# LoRa_E32_STM32F4.net
KiCad netlist of a schematic drawn in EAGLE
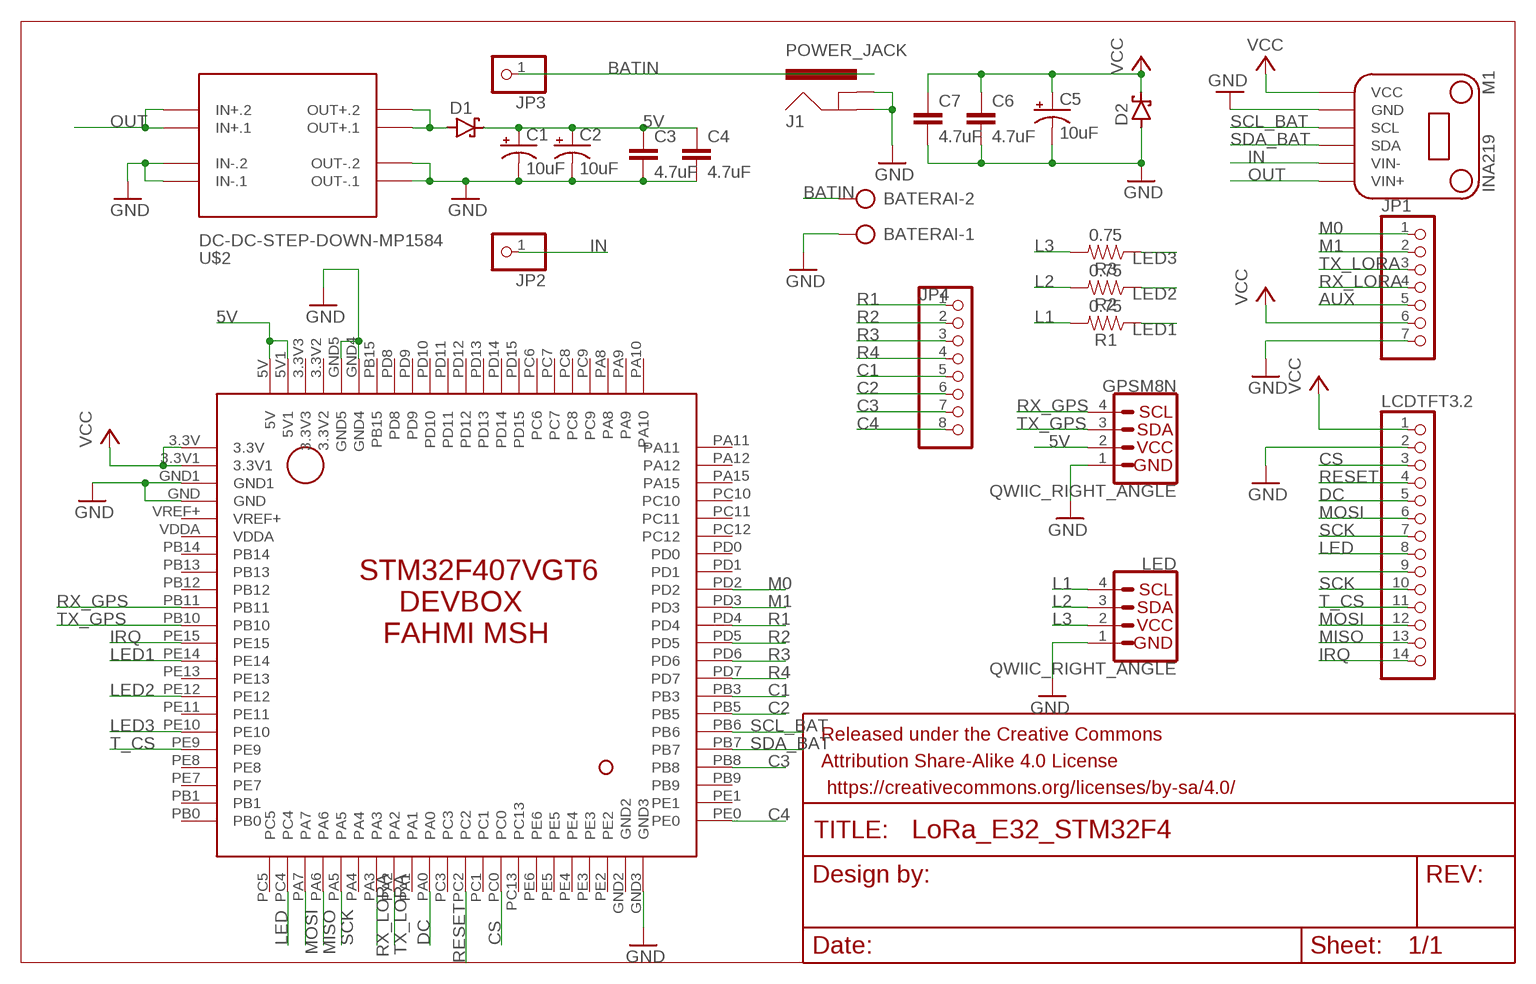
[diagram p0: schematic, sheet 1]

(export (version "E")
  (design (tool "Eeschema 10.0.6"))
  (components
    (comp (ref "BATERAI")
      (value "AK500/2")
      (footprint "eagle-import:AK500_2")
      (libsource (lib "eagle-import") (part "AK500/2"))
    )
    (comp (ref "C1")
      (value "10uF")
      (footprint "eagle-import:EIA3216")
      (libsource (lib "eagle-import") (part "10UF-POLAR-EIA3216-16V-10%(TANT)"))
    )
    (comp (ref "C2")
      (value "10uF")
      (footprint "eagle-import:EIA3216")
      (libsource (lib "eagle-import") (part "10UF-POLAR-EIA3216-16V-10%(TANT)"))
    )
    (comp (ref "C3")
      (value "4.7uF")
      (footprint "eagle-import:0805")
      (libsource (lib "eagle-import") (part "4.7UF-0805-50V-(10%)"))
    )
    (comp (ref "C4")
      (value "4.7uF")
      (footprint "eagle-import:0805")
      (libsource (lib "eagle-import") (part "4.7UF-0805-50V-(10%)"))
    )
    (comp (ref "C5")
      (value "10uF")
      (footprint "eagle-import:EIA3216")
      (libsource (lib "eagle-import") (part "10UF-POLAR-EIA3216-16V-10%(TANT)"))
    )
    (comp (ref "C6")
      (value "4.7uF")
      (footprint "eagle-import:0805")
      (libsource (lib "eagle-import") (part "4.7UF-0805-50V-(10%)"))
    )
    (comp (ref "C7")
      (value "4.7uF")
      (footprint "eagle-import:0805")
      (libsource (lib "eagle-import") (part "4.7UF-0805-50V-(10%)"))
    )
    (comp (ref "D1")
      (value "SCHOTTKY-DIODESMD")
      (footprint "eagle-import:SMB")
      (libsource (lib "eagle-import") (part "SCHOTTKY-DIODESMD"))
    )
    (comp (ref "D2")
      (value "SCHOTTKY-DIODESMD")
      (footprint "eagle-import:SMB")
      (libsource (lib "eagle-import") (part "SCHOTTKY-DIODESMD"))
    )
    (comp (ref "FRAME1")
      (value "FRAME-LEDGER")
      (footprint "eagle-import:CREATIVE_COMMONS")
      (libsource (lib "eagle-import") (part "FRAME-LEDGER"))
    )
    (comp (ref "GPSM8N")
      (value "QWIIC_RIGHT_ANGLE")
      (footprint "eagle-import:JST04_1MM_RA")
      (libsource (lib "eagle-import") (part "QWIIC_CONNECTORJS-1MM"))
    )
    (comp (ref "J1")
      (value "POWER_JACK")
      (footprint "eagle-import:POWER_JACK_PTH")
      (libsource (lib "eagle-import") (part "POWER_JACK"))
    )
    (comp (ref "JP1")
      (value "PINHD-1X7")
      (footprint "eagle-import:1X07")
      (libsource (lib "eagle-import") (part "PINHD-1X7"))
    )
    (comp (ref "JP2")
      (value "PINHD-1X1")
      (footprint "eagle-import:1X01")
      (libsource (lib "eagle-import") (part "PINHD-1X1"))
    )
    (comp (ref "JP3")
      (value "PINHD-1X1")
      (footprint "eagle-import:1X01")
      (libsource (lib "eagle-import") (part "PINHD-1X1"))
    )
    (comp (ref "JP4")
      (value "PINHD-1X8/90")
      (footprint "eagle-import:1X08_90")
      (libsource (lib "eagle-import") (part "PINHD-1X8/90"))
    )
    (comp (ref "LCDTFT3.2")
      (value "PINHD-1X14")
      (footprint "eagle-import:1X14")
      (libsource (lib "eagle-import") (part "PINHD-1X14"))
    )
    (comp (ref "LED")
      (value "QWIIC_RIGHT_ANGLE")
      (footprint "eagle-import:JST04_1MM_RA")
      (libsource (lib "eagle-import") (part "QWIIC_CONNECTORJS-1MM"))
    )
    (comp (ref "M1")
      (value "INA219")
      (footprint "eagle-import:INA219")
      (libsource (lib "eagle-import") (part "INA219"))
    )
    (comp (ref "R1")
      (value "0.75")
      (footprint "eagle-import:0805")
      (libsource (lib "eagle-import") (part "0.75OHM-0805-1/4W-1%"))
    )
    (comp (ref "R2")
      (value "0.75")
      (footprint "eagle-import:0805")
      (libsource (lib "eagle-import") (part "0.75OHM-0805-1/4W-1%"))
    )
    (comp (ref "R3")
      (value "0.75")
      (footprint "eagle-import:0805")
      (libsource (lib "eagle-import") (part "0.75OHM-0805-1/4W-1%"))
    )
    (comp (ref "U$1")
      (value "STM32F4DEVBOX")
      (footprint "eagle-import:STM32F4DEVBOX")
      (libsource (lib "eagle-import") (part "STM32F4DEVBOX"))
    )
    (comp (ref "U$2")
      (value "DC-DC-STEP-DOWN-MP1584")
      (footprint "eagle-import:DC-DC-STEP-DOWN-MP1584")
      (libsource (lib "eagle-import") (part "DC-DC-STEP-DOWN-MP1584"))
    )
  )
  (nets
    (net (code "1") (name "/5V") (class "Default")
      (node (ref "C1") (pin "+") (pinfunction "+_+") (pintype "passive"))
      (node (ref "C2") (pin "+") (pinfunction "+_+") (pintype "passive"))
      (node (ref "C3") (pin "1") (pinfunction "1_1") (pintype "passive"))
      (node (ref "C4") (pin "1") (pinfunction "1_1") (pintype "passive"))
      (node (ref "D1") (pin "C") (pinfunction "C_C") (pintype "passive"))
      (node (ref "GPSM8N") (pin "2") (pinfunction "2_2") (pintype "power_in"))
      (node (ref "U$1") (pin "5V") (pinfunction "5V_5V") (pintype "bidirectional"))
      (node (ref "U$1") (pin "5V1") (pinfunction "5V1_5V1") (pintype "bidirectional"))
    )
    (net (code "2") (name "/AUX") (class "Default")
      (node (ref "JP1") (pin "5") (pinfunction "5_5") (pintype "passive"))
    )
    (net (code "3") (name "/BATIN") (class "Default")
      (node (ref "BATERAI") (pin "2") (pinfunction "KL_2") (pintype "passive"))
      (node (ref "J1") (pin "PWR") (pinfunction "PWR_PWR") (pintype "bidirectional"))
      (node (ref "JP3") (pin "1") (pinfunction "1_1") (pintype "passive"))
    )
    (net (code "4") (name "/C1") (class "Default")
      (node (ref "JP4") (pin "5") (pinfunction "5_5") (pintype "passive"))
      (node (ref "U$1") (pin "PB3") (pinfunction "PB3_PB3") (pintype "bidirectional"))
    )
    (net (code "5") (name "/C2") (class "Default")
      (node (ref "JP4") (pin "6") (pinfunction "6_6") (pintype "passive"))
      (node (ref "U$1") (pin "PB5") (pinfunction "PB5_PB5") (pintype "bidirectional"))
    )
    (net (code "6") (name "/C3") (class "Default")
      (node (ref "JP4") (pin "7") (pinfunction "7_7") (pintype "passive"))
      (node (ref "U$1") (pin "PB8") (pinfunction "PB8_PB8") (pintype "bidirectional"))
    )
    (net (code "7") (name "/C4") (class "Default")
      (node (ref "JP4") (pin "8") (pinfunction "8_8") (pintype "passive"))
      (node (ref "U$1") (pin "PE0") (pinfunction "PE0_PE0") (pintype "bidirectional"))
    )
    (net (code "8") (name "/CS") (class "Default")
      (node (ref "LCDTFT3.2") (pin "3") (pinfunction "3_3") (pintype "passive"))
      (node (ref "U$1") (pin "PC0") (pinfunction "PC0_PC0") (pintype "bidirectional"))
    )
    (net (code "9") (name "/DC") (class "Default")
      (node (ref "LCDTFT3.2") (pin "5") (pinfunction "5_5") (pintype "passive"))
      (node (ref "U$1") (pin "PA0") (pinfunction "PA0_PA0") (pintype "bidirectional"))
    )
    (net (code "10") (name "/IN") (class "Default")
      (node (ref "JP2") (pin "1") (pinfunction "1_1") (pintype "passive"))
      (node (ref "M1") (pin "VIN-") (pinfunction "VIN-_VIN-") (pintype "bidirectional"))
    )
    (net (code "11") (name "/IRQ") (class "Default")
      (node (ref "LCDTFT3.2") (pin "14") (pinfunction "14_14") (pintype "passive"))
      (node (ref "U$1") (pin "PE15") (pinfunction "PE15_PE15") (pintype "bidirectional"))
    )
    (net (code "12") (name "/L1") (class "Default")
      (node (ref "LED") (pin "4") (pinfunction "4_4") (pintype "passive"))
      (node (ref "R1") (pin "2") (pinfunction "2_2") (pintype "passive"))
    )
    (net (code "13") (name "/L2") (class "Default")
      (node (ref "LED") (pin "3") (pinfunction "3_3") (pintype "passive"))
      (node (ref "R2") (pin "2") (pinfunction "2_2") (pintype "passive"))
    )
    (net (code "14") (name "/L3") (class "Default")
      (node (ref "LED") (pin "2") (pinfunction "2_2") (pintype "power_in"))
      (node (ref "R3") (pin "2") (pinfunction "2_2") (pintype "passive"))
    )
    (net (code "15") (name "/LED") (class "Default")
      (node (ref "LCDTFT3.2") (pin "8") (pinfunction "8_8") (pintype "passive"))
      (node (ref "U$1") (pin "PC4") (pinfunction "PC4_PC4") (pintype "bidirectional"))
    )
    (net (code "16") (name "/LED1") (class "Default")
      (node (ref "R1") (pin "1") (pinfunction "1_1") (pintype "passive"))
      (node (ref "U$1") (pin "PE14") (pinfunction "PE14_PE14") (pintype "bidirectional"))
    )
    (net (code "17") (name "/LED2") (class "Default")
      (node (ref "R2") (pin "1") (pinfunction "1_1") (pintype "passive"))
      (node (ref "U$1") (pin "PE12") (pinfunction "PE12_PE12") (pintype "bidirectional"))
    )
    (net (code "18") (name "/LED3") (class "Default")
      (node (ref "R3") (pin "1") (pinfunction "1_1") (pintype "passive"))
      (node (ref "U$1") (pin "PE10") (pinfunction "PE10_PE10") (pintype "bidirectional"))
    )
    (net (code "19") (name "/M0") (class "Default")
      (node (ref "JP1") (pin "1") (pinfunction "1_1") (pintype "passive"))
      (node (ref "U$1") (pin "PD2") (pinfunction "PD2_PD2") (pintype "bidirectional"))
    )
    (net (code "20") (name "/M1") (class "Default")
      (node (ref "JP1") (pin "2") (pinfunction "2_2") (pintype "passive"))
      (node (ref "U$1") (pin "PD3") (pinfunction "PD3_PD3") (pintype "bidirectional"))
    )
    (net (code "21") (name "/MISO") (class "Default")
      (node (ref "LCDTFT3.2") (pin "13") (pinfunction "13_13") (pintype "passive"))
      (node (ref "U$1") (pin "PA6") (pinfunction "PA6_PA6") (pintype "bidirectional"))
    )
    (net (code "22") (name "/MOSI") (class "Default")
      (node (ref "LCDTFT3.2") (pin "12") (pinfunction "12_12") (pintype "passive"))
      (node (ref "LCDTFT3.2") (pin "6") (pinfunction "6_6") (pintype "passive"))
      (node (ref "U$1") (pin "PA7") (pinfunction "PA7_PA7") (pintype "bidirectional"))
    )
    (net (code "23") (name "/OUT") (class "Default")
      (node (ref "M1") (pin "VIN+") (pinfunction "VIN+_VIN+") (pintype "bidirectional"))
      (node (ref "U$2") (pin "IN+.1") (pinfunction "IN+.1_IN+.1") (pintype "bidirectional"))
      (node (ref "U$2") (pin "IN+.2") (pinfunction "IN+.2_IN+.2") (pintype "bidirectional"))
    )
    (net (code "24") (name "/R1") (class "Default")
      (node (ref "JP4") (pin "1") (pinfunction "1_1") (pintype "passive"))
      (node (ref "U$1") (pin "PD4") (pinfunction "PD4_PD4") (pintype "bidirectional"))
    )
    (net (code "25") (name "/R2") (class "Default")
      (node (ref "JP4") (pin "2") (pinfunction "2_2") (pintype "passive"))
      (node (ref "U$1") (pin "PD5") (pinfunction "PD5_PD5") (pintype "bidirectional"))
    )
    (net (code "26") (name "/R3") (class "Default")
      (node (ref "JP4") (pin "3") (pinfunction "3_3") (pintype "passive"))
      (node (ref "U$1") (pin "PD6") (pinfunction "PD6_PD6") (pintype "bidirectional"))
    )
    (net (code "27") (name "/R4") (class "Default")
      (node (ref "JP4") (pin "4") (pinfunction "4_4") (pintype "passive"))
      (node (ref "U$1") (pin "PD7") (pinfunction "PD7_PD7") (pintype "bidirectional"))
    )
    (net (code "28") (name "/RESET") (class "Default")
      (node (ref "LCDTFT3.2") (pin "4") (pinfunction "4_4") (pintype "passive"))
      (node (ref "U$1") (pin "PC2") (pinfunction "PC2_PC2") (pintype "bidirectional"))
    )
    (net (code "29") (name "/RX_GPS") (class "Default")
      (node (ref "GPSM8N") (pin "4") (pinfunction "4_4") (pintype "passive"))
      (node (ref "U$1") (pin "PB11") (pinfunction "PB11_PB11") (pintype "bidirectional"))
    )
    (net (code "30") (name "/RX_LORA") (class "Default")
      (node (ref "JP1") (pin "4") (pinfunction "4_4") (pintype "passive"))
      (node (ref "U$1") (pin "PA3") (pinfunction "PA3_PA3") (pintype "bidirectional"))
    )
    (net (code "31") (name "/SCK") (class "Default")
      (node (ref "LCDTFT3.2") (pin "10") (pinfunction "10_10") (pintype "passive"))
      (node (ref "LCDTFT3.2") (pin "7") (pinfunction "7_7") (pintype "passive"))
      (node (ref "U$1") (pin "PA5") (pinfunction "PA5_PA5") (pintype "bidirectional"))
    )
    (net (code "32") (name "/SCL_BAT") (class "Default")
      (node (ref "M1") (pin "SCL") (pinfunction "SCL_SCL") (pintype "bidirectional"))
      (node (ref "U$1") (pin "PB6") (pinfunction "PB6_PB6") (pintype "bidirectional"))
    )
    (net (code "33") (name "/SDA_BAT") (class "Default")
      (node (ref "M1") (pin "SDA") (pinfunction "SDA_SDA") (pintype "bidirectional"))
      (node (ref "U$1") (pin "PB7") (pinfunction "PB7_PB7") (pintype "bidirectional"))
    )
    (net (code "34") (name "/TX_GPS") (class "Default")
      (node (ref "GPSM8N") (pin "3") (pinfunction "3_3") (pintype "passive"))
      (node (ref "U$1") (pin "PB10") (pinfunction "PB10_PB10") (pintype "bidirectional"))
    )
    (net (code "35") (name "/TX_LORA") (class "Default")
      (node (ref "JP1") (pin "3") (pinfunction "3_3") (pintype "passive"))
      (node (ref "U$1") (pin "PA2") (pinfunction "PA2_PA2") (pintype "bidirectional"))
    )
    (net (code "36") (name "/T_CS") (class "Default")
      (node (ref "LCDTFT3.2") (pin "11") (pinfunction "11_11") (pintype "passive"))
      (node (ref "U$1") (pin "PE9") (pinfunction "PE9_PE9") (pintype "bidirectional"))
    )
    (net (code "37") (name "GND") (class "Default")
      (node (ref "BATERAI") (pin "1") (pinfunction "KL_1") (pintype "passive"))
      (node (ref "C1") (pin "-") (pinfunction "-_-") (pintype "passive"))
      (node (ref "C2") (pin "-") (pinfunction "-_-") (pintype "passive"))
      (node (ref "C3") (pin "2") (pinfunction "2_2") (pintype "passive"))
      (node (ref "C4") (pin "2") (pinfunction "2_2") (pintype "passive"))
      (node (ref "C5") (pin "-") (pinfunction "-_-") (pintype "passive"))
      (node (ref "C6") (pin "2") (pinfunction "2_2") (pintype "passive"))
      (node (ref "C7") (pin "2") (pinfunction "2_2") (pintype "passive"))
      (node (ref "D2") (pin "A") (pinfunction "A_A") (pintype "passive"))
      (node (ref "GPSM8N") (pin "1") (pinfunction "1_1") (pintype "power_in"))
      (node (ref "J1") (pin "GND") (pinfunction "GND_GND") (pintype "bidirectional"))
      (node (ref "J1") (pin "GNDBREAK") (pinfunction "GNDBREAK_GNDBREAK") (pintype "bidirectional"))
      (node (ref "JP1") (pin "7") (pinfunction "7_7") (pintype "passive"))
      (node (ref "LCDTFT3.2") (pin "2") (pinfunction "2_2") (pintype "passive"))
      (node (ref "LED") (pin "1") (pinfunction "1_1") (pintype "power_in"))
      (node (ref "M1") (pin "GND") (pinfunction "GND_GND") (pintype "bidirectional"))
      (node (ref "U$1") (pin "GND") (pinfunction "GND_GND") (pintype "bidirectional"))
      (node (ref "U$1") (pin "GND1") (pinfunction "GND1_GND1") (pintype "bidirectional"))
      (node (ref "U$1") (pin "GND3") (pinfunction "GND3_GND3") (pintype "bidirectional"))
      (node (ref "U$1") (pin "GND4") (pinfunction "GND4_GND4") (pintype "bidirectional"))
      (node (ref "U$1") (pin "GND5") (pinfunction "GND5_GND5") (pintype "bidirectional"))
      (node (ref "U$2") (pin "IN-.1") (pinfunction "IN-.1_IN-.1") (pintype "bidirectional"))
      (node (ref "U$2") (pin "IN-.2") (pinfunction "IN-.2_IN-.2") (pintype "bidirectional"))
      (node (ref "U$2") (pin "OUT-.1") (pinfunction "OUT-.1_OUT-.1") (pintype "bidirectional"))
      (node (ref "U$2") (pin "OUT-.2") (pinfunction "OUT-.2_OUT-.2") (pintype "bidirectional"))
    )
    (net (code "38") (name "Net-(D1-PadA)") (class "Default")
      (node (ref "D1") (pin "A") (pinfunction "A_A") (pintype "passive"))
      (node (ref "U$2") (pin "OUT+.1") (pinfunction "OUT+.1_OUT+.1") (pintype "bidirectional"))
      (node (ref "U$2") (pin "OUT+.2") (pinfunction "OUT+.2_OUT+.2") (pintype "bidirectional"))
    )
    (net (code "39") (name "VCC") (class "Default")
      (node (ref "C5") (pin "+") (pinfunction "+_+") (pintype "passive"))
      (node (ref "C6") (pin "1") (pinfunction "1_1") (pintype "passive"))
      (node (ref "C7") (pin "1") (pinfunction "1_1") (pintype "passive"))
      (node (ref "D2") (pin "C") (pinfunction "C_C") (pintype "passive"))
      (node (ref "JP1") (pin "6") (pinfunction "6_6") (pintype "passive"))
      (node (ref "LCDTFT3.2") (pin "1") (pinfunction "1_1") (pintype "passive"))
      (node (ref "M1") (pin "VCC") (pinfunction "VCC_VCC") (pintype "bidirectional"))
      (node (ref "U$1") (pin "3.3V") (pinfunction "3.3V_3.3V") (pintype "bidirectional"))
      (node (ref "U$1") (pin "3.3V1") (pinfunction "3.3V1_3.3V1") (pintype "bidirectional"))
    )
    (net (code "40") (name "unconnected-(LCDTFT3.2-Pad9)") (class "Default")
      (node (ref "LCDTFT3.2") (pin "9") (pinfunction "9_9") (pintype "passive"))
    )
    (net (code "41") (name "unconnected-(U$1-Pad3.3V2)") (class "Default")
      (node (ref "U$1") (pin "3.3V2") (pinfunction "3.3V2_3.3V2") (pintype "bidirectional"))
    )
    (net (code "42") (name "unconnected-(U$1-Pad3.3V3)") (class "Default")
      (node (ref "U$1") (pin "3.3V3") (pinfunction "3.3V3_3.3V3") (pintype "bidirectional"))
    )
    (net (code "43") (name "unconnected-(U$1-PadGND2)") (class "Default")
      (node (ref "U$1") (pin "GND2") (pinfunction "GND2_GND2") (pintype "bidirectional"))
    )
    (net (code "44") (name "unconnected-(U$1-PadPA1)") (class "Default")
      (node (ref "U$1") (pin "PA1") (pinfunction "PA1_PA1") (pintype "bidirectional"))
    )
    (net (code "45") (name "unconnected-(U$1-PadPA4)") (class "Default")
      (node (ref "U$1") (pin "PA4") (pinfunction "PA4_PA4") (pintype "bidirectional"))
    )
    (net (code "46") (name "unconnected-(U$1-PadPA8)") (class "Default")
      (node (ref "U$1") (pin "PA8") (pinfunction "PA8_PA8") (pintype "bidirectional"))
    )
    (net (code "47") (name "unconnected-(U$1-PadPA9)") (class "Default")
      (node (ref "U$1") (pin "PA9") (pinfunction "PA9_PA9") (pintype "bidirectional"))
    )
    (net (code "48") (name "unconnected-(U$1-PadPA10)") (class "Default")
      (node (ref "U$1") (pin "PA10") (pinfunction "PA10_PA10") (pintype "bidirectional"))
    )
    (net (code "49") (name "unconnected-(U$1-PadPA11)") (class "Default")
      (node (ref "U$1") (pin "PA11") (pinfunction "PA11_PA11") (pintype "bidirectional"))
    )
    (net (code "50") (name "unconnected-(U$1-PadPA12)") (class "Default")
      (node (ref "U$1") (pin "PA12") (pinfunction "PA12_PA12") (pintype "bidirectional"))
    )
    (net (code "51") (name "unconnected-(U$1-PadPA15)") (class "Default")
      (node (ref "U$1") (pin "PA15") (pinfunction "PA15_PA15") (pintype "bidirectional"))
    )
    (net (code "52") (name "unconnected-(U$1-PadPB0)") (class "Default")
      (node (ref "U$1") (pin "PB0") (pinfunction "PB0_PB0") (pintype "bidirectional"))
    )
    (net (code "53") (name "unconnected-(U$1-PadPB1)") (class "Default")
      (node (ref "U$1") (pin "PB1") (pinfunction "PB1_PB1") (pintype "bidirectional"))
    )
    (net (code "54") (name "unconnected-(U$1-PadPB9)") (class "Default")
      (node (ref "U$1") (pin "PB9") (pinfunction "PB9_PB9") (pintype "bidirectional"))
    )
    (net (code "55") (name "unconnected-(U$1-PadPB12)") (class "Default")
      (node (ref "U$1") (pin "PB12") (pinfunction "PB12_PB12") (pintype "bidirectional"))
    )
    (net (code "56") (name "unconnected-(U$1-PadPB13)") (class "Default")
      (node (ref "U$1") (pin "PB13") (pinfunction "PB13_PB13") (pintype "bidirectional"))
    )
    (net (code "57") (name "unconnected-(U$1-PadPB14)") (class "Default")
      (node (ref "U$1") (pin "PB14") (pinfunction "PB14_PB14") (pintype "bidirectional"))
    )
    (net (code "58") (name "unconnected-(U$1-PadPB15)") (class "Default")
      (node (ref "U$1") (pin "PB15") (pinfunction "PB15_PB15") (pintype "bidirectional"))
    )
    (net (code "59") (name "unconnected-(U$1-PadPC1)") (class "Default")
      (node (ref "U$1") (pin "PC1") (pinfunction "PC1_PC1") (pintype "bidirectional"))
    )
    (net (code "60") (name "unconnected-(U$1-PadPC3)") (class "Default")
      (node (ref "U$1") (pin "PC3") (pinfunction "PC3_PC3") (pintype "bidirectional"))
    )
    (net (code "61") (name "unconnected-(U$1-PadPC5)") (class "Default")
      (node (ref "U$1") (pin "PC5") (pinfunction "PC5_PC5") (pintype "bidirectional"))
    )
    (net (code "62") (name "unconnected-(U$1-PadPC6)") (class "Default")
      (node (ref "U$1") (pin "PC6") (pinfunction "PC6_PC6") (pintype "bidirectional"))
    )
    (net (code "63") (name "unconnected-(U$1-PadPC7)") (class "Default")
      (node (ref "U$1") (pin "PC7") (pinfunction "PC7_PC7") (pintype "bidirectional"))
    )
    (net (code "64") (name "unconnected-(U$1-PadPC8)") (class "Default")
      (node (ref "U$1") (pin "PC8") (pinfunction "PC8_PC8") (pintype "bidirectional"))
    )
    (net (code "65") (name "unconnected-(U$1-PadPC9)") (class "Default")
      (node (ref "U$1") (pin "PC9") (pinfunction "PC9_PC9") (pintype "bidirectional"))
    )
    (net (code "66") (name "unconnected-(U$1-PadPC10)") (class "Default")
      (node (ref "U$1") (pin "PC10") (pinfunction "PC10_PC10") (pintype "bidirectional"))
    )
    (net (code "67") (name "unconnected-(U$1-PadPC11)") (class "Default")
      (node (ref "U$1") (pin "PC11") (pinfunction "PC11_PC11") (pintype "bidirectional"))
    )
    (net (code "68") (name "unconnected-(U$1-PadPC12)") (class "Default")
      (node (ref "U$1") (pin "PC12") (pinfunction "PC12_PC12") (pintype "bidirectional"))
    )
    (net (code "69") (name "unconnected-(U$1-PadPC13)") (class "Default")
      (node (ref "U$1") (pin "PC13") (pinfunction "PC13_PC13") (pintype "bidirectional"))
    )
    (net (code "70") (name "unconnected-(U$1-PadPD0)") (class "Default")
      (node (ref "U$1") (pin "PD0") (pinfunction "PD0_PD0") (pintype "bidirectional"))
    )
    (net (code "71") (name "unconnected-(U$1-PadPD1)") (class "Default")
      (node (ref "U$1") (pin "PD1") (pinfunction "PD1_PD1") (pintype "bidirectional"))
    )
    (net (code "72") (name "unconnected-(U$1-PadPD8)") (class "Default")
      (node (ref "U$1") (pin "PD8") (pinfunction "PD8_PD8") (pintype "bidirectional"))
    )
    (net (code "73") (name "unconnected-(U$1-PadPD9)") (class "Default")
      (node (ref "U$1") (pin "PD9") (pinfunction "PD9_PD9") (pintype "bidirectional"))
    )
    (net (code "74") (name "unconnected-(U$1-PadPD10)") (class "Default")
      (node (ref "U$1") (pin "PD10") (pinfunction "PD10_PD10") (pintype "bidirectional"))
    )
    (net (code "75") (name "unconnected-(U$1-PadPD11)") (class "Default")
      (node (ref "U$1") (pin "PD11") (pinfunction "PD11_PD11") (pintype "bidirectional"))
    )
    (net (code "76") (name "unconnected-(U$1-PadPD12)") (class "Default")
      (node (ref "U$1") (pin "PD12") (pinfunction "PD12_PD12") (pintype "bidirectional"))
    )
    (net (code "77") (name "unconnected-(U$1-PadPD13)") (class "Default")
      (node (ref "U$1") (pin "PD13") (pinfunction "PD13_PD13") (pintype "bidirectional"))
    )
    (net (code "78") (name "unconnected-(U$1-PadPD14)") (class "Default")
      (node (ref "U$1") (pin "PD14") (pinfunction "PD14_PD14") (pintype "bidirectional"))
    )
    (net (code "79") (name "unconnected-(U$1-PadPD15)") (class "Default")
      (node (ref "U$1") (pin "PD15") (pinfunction "PD15_PD15") (pintype "bidirectional"))
    )
    (net (code "80") (name "unconnected-(U$1-PadPE1)") (class "Default")
      (node (ref "U$1") (pin "PE1") (pinfunction "PE1_PE1") (pintype "bidirectional"))
    )
    (net (code "81") (name "unconnected-(U$1-PadPE2)") (class "Default")
      (node (ref "U$1") (pin "PE2") (pinfunction "PE2_PE2") (pintype "bidirectional"))
    )
    (net (code "82") (name "unconnected-(U$1-PadPE3)") (class "Default")
      (node (ref "U$1") (pin "PE3") (pinfunction "PE3_PE3") (pintype "bidirectional"))
    )
    (net (code "83") (name "unconnected-(U$1-PadPE4)") (class "Default")
      (node (ref "U$1") (pin "PE4") (pinfunction "PE4_PE4") (pintype "bidirectional"))
    )
    (net (code "84") (name "unconnected-(U$1-PadPE5)") (class "Default")
      (node (ref "U$1") (pin "PE5") (pinfunction "PE5_PE5") (pintype "bidirectional"))
    )
    (net (code "85") (name "unconnected-(U$1-PadPE6)") (class "Default")
      (node (ref "U$1") (pin "PE6") (pinfunction "PE6_PE6") (pintype "bidirectional"))
    )
    (net (code "86") (name "unconnected-(U$1-PadPE7)") (class "Default")
      (node (ref "U$1") (pin "PE7") (pinfunction "PE7_PE7") (pintype "bidirectional"))
    )
    (net (code "87") (name "unconnected-(U$1-PadPE8)") (class "Default")
      (node (ref "U$1") (pin "PE8") (pinfunction "PE8_PE8") (pintype "bidirectional"))
    )
    (net (code "88") (name "unconnected-(U$1-PadPE11)") (class "Default")
      (node (ref "U$1") (pin "PE11") (pinfunction "PE11_PE11") (pintype "bidirectional"))
    )
    (net (code "89") (name "unconnected-(U$1-PadPE13)") (class "Default")
      (node (ref "U$1") (pin "PE13") (pinfunction "PE13_PE13") (pintype "bidirectional"))
    )
    (net (code "90") (name "unconnected-(U$1-PadVDDA)") (class "Default")
      (node (ref "U$1") (pin "VDDA") (pinfunction "VDDA_VDDA") (pintype "bidirectional"))
    )
    (net (code "91") (name "unconnected-(U$1-PadVREF+)") (class "Default")
      (node (ref "U$1") (pin "VREF+") (pinfunction "VREF+_VREF+") (pintype "bidirectional"))
    )
  )
)
